# supply.net
KiCad netlist of a schematic drawn in Altium Designer
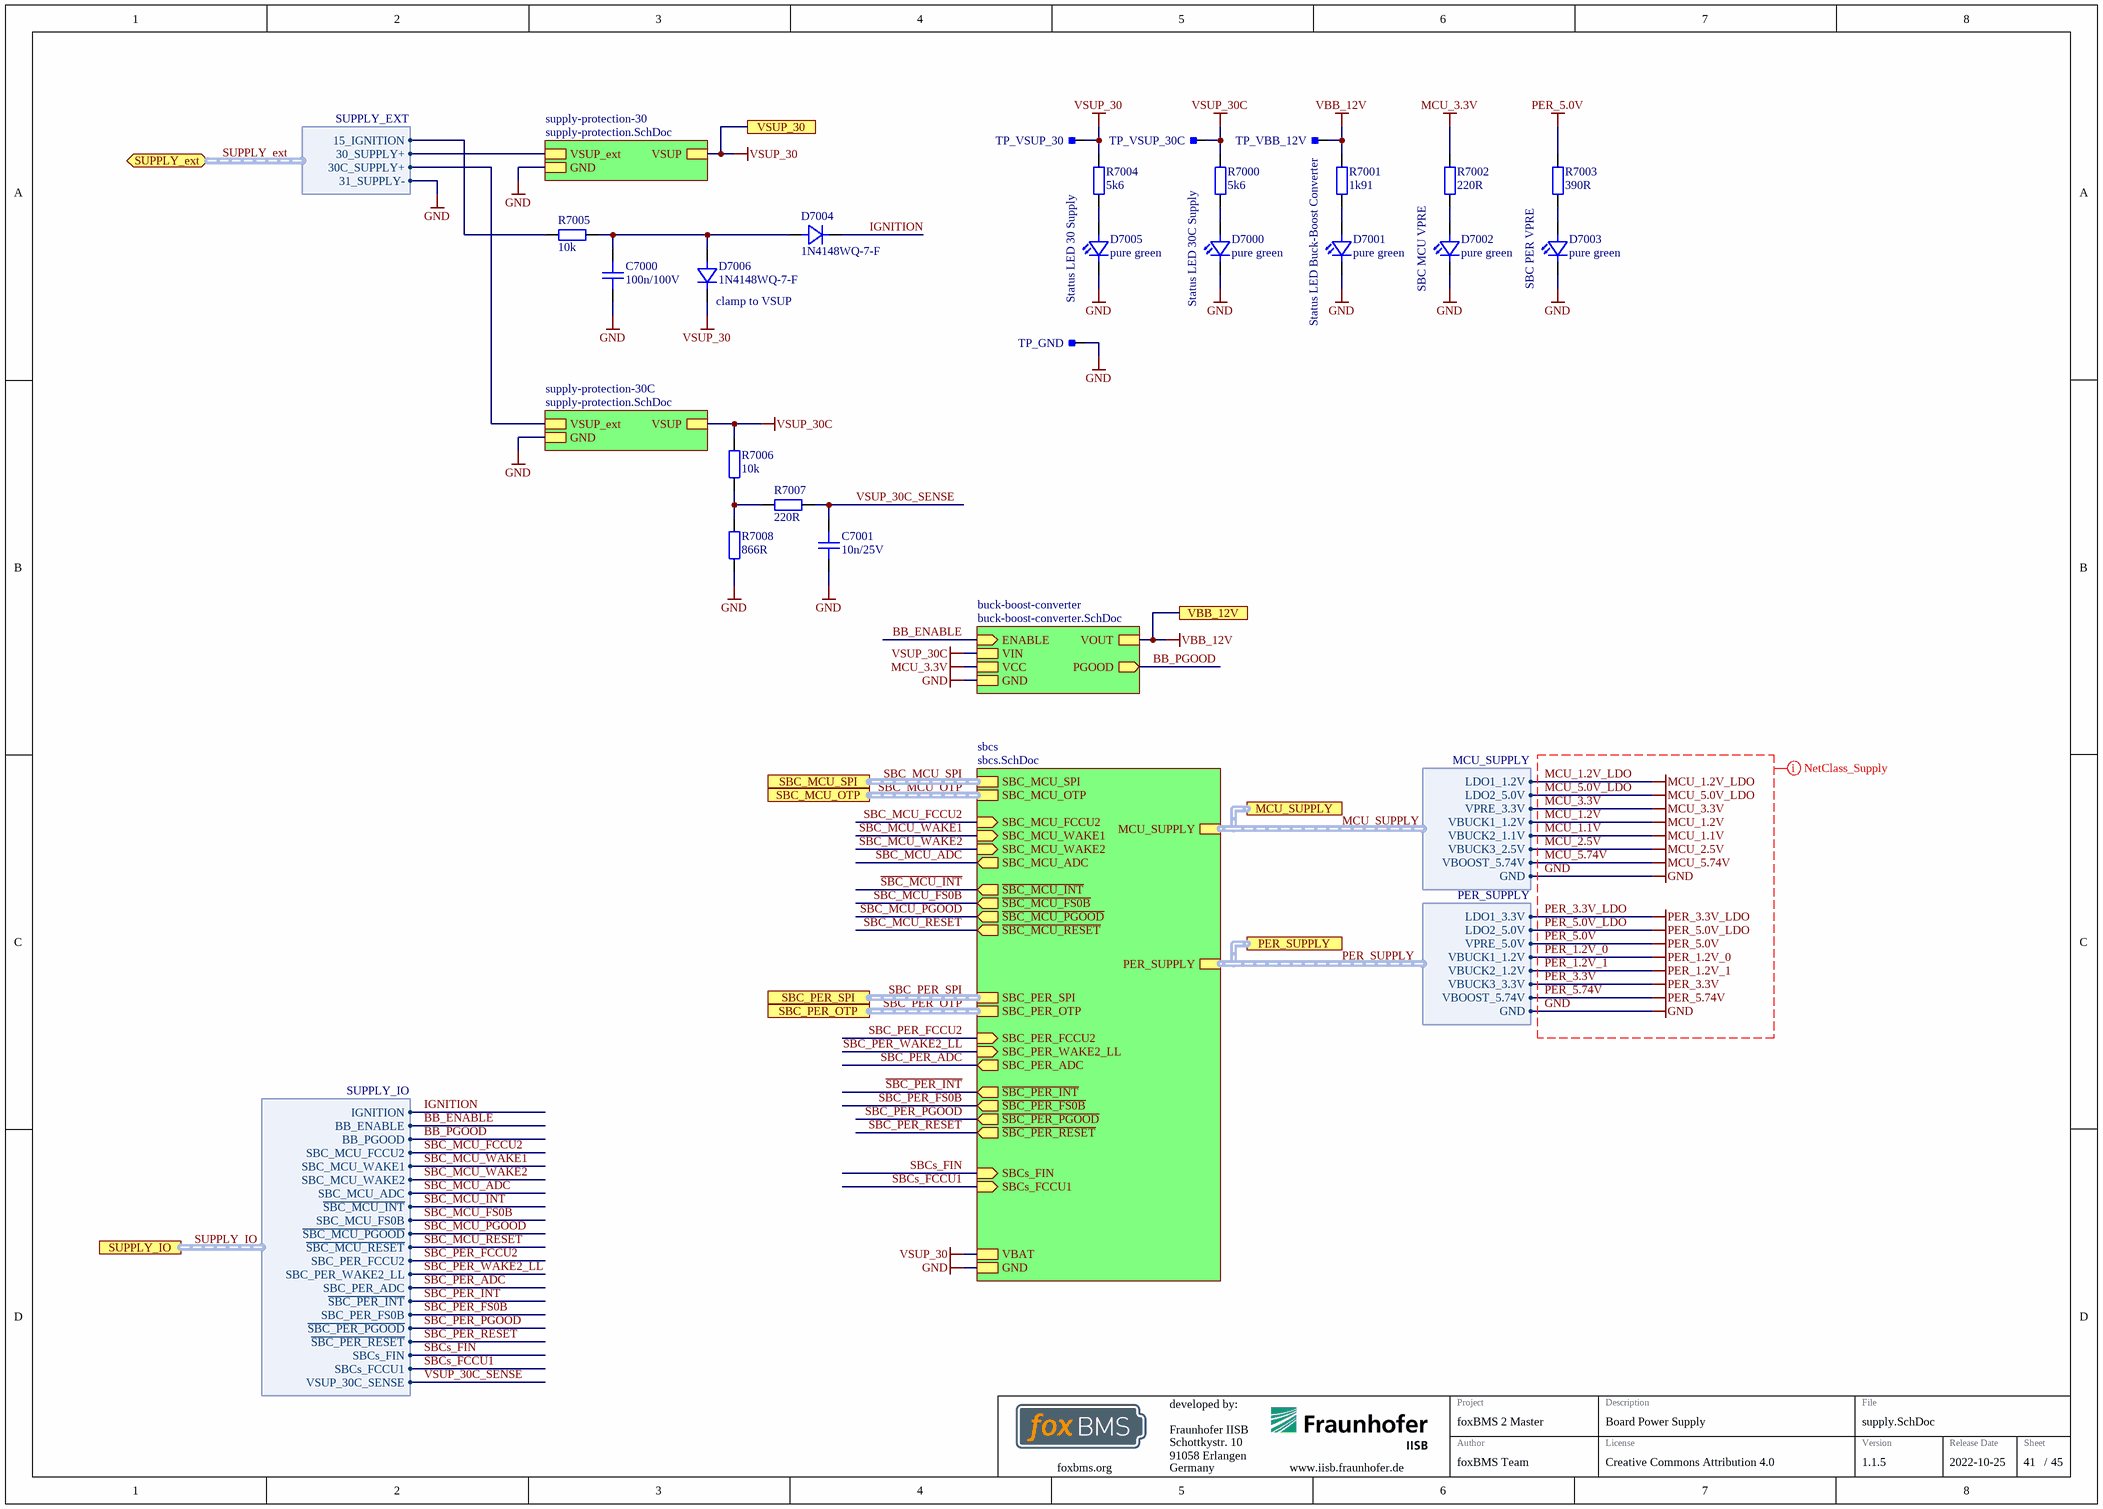
[diagram p0: supply.SchDoc]

(export (version "E")
  (design (tool "Eeschema 10.0.6"))
  (components
    (comp (ref "C7000")
      (value "100n/100V")
      (footprint "CAPC1608X08N")
      (description "MLCC")
      (fields (field (name "PART NUMBER") "gen_C_ceramic_100n_100V_X7R_0603"))
      (libsource (lib "OE750") (part "C"))
    )
    (comp (ref "C7001")
      (value "10n/25V")
      (footprint "CAPC1005X06N")
      (description "MLCC")
      (fields (field (name "PART NUMBER") "gen_C_ceramic_10n_25V_X7R_0402"))
      (libsource (lib "OE750") (part "C"))
    )
    (comp (ref "D7000")
      (value "pure green")
      (footprint "LEDC1608X07N")
      (description "TLMP1100-GS08")
      (fields (field (name "PART NUMBER") "LED_0603_pure_green_AECQ") (field (name "MANUFACTURER") "Vishay"))
      (libsource (lib "OE750") (part "D_LED"))
    )
    (comp (ref "D7001")
      (value "pure green")
      (footprint "LEDC1608X07N")
      (description "TLMP1100-GS08")
      (fields (field (name "PART NUMBER") "LED_0603_pure_green_AECQ") (field (name "MANUFACTURER") "Vishay"))
      (libsource (lib "OE750") (part "D_LED"))
    )
    (comp (ref "D7002")
      (value "pure green")
      (footprint "LEDC1608X07N")
      (description "TLMP1100-GS08")
      (fields (field (name "PART NUMBER") "LED_0603_pure_green_AECQ") (field (name "MANUFACTURER") "Vishay"))
      (libsource (lib "OE750") (part "D_LED"))
    )
    (comp (ref "D7003")
      (value "pure green")
      (footprint "LEDC1608X07N")
      (description "TLMP1100-GS08")
      (fields (field (name "PART NUMBER") "LED_0603_pure_green_AECQ") (field (name "MANUFACTURER") "Vishay"))
      (libsource (lib "OE750") (part "D_LED"))
    )
    (comp (ref "D7004")
      (value "1N4148WQ-7-F")
      (footprint "SOD-123_CASE-425-04-ISSUE-G")
      (description "Diode")
      (fields (field (name "MANUFACTURER") "Diodes Inc."))
      (libsource (lib "OE750") (part "D"))
    )
    (comp (ref "D7005")
      (value "pure green")
      (footprint "LEDC1608X07N")
      (description "TLMP1100-GS08")
      (fields (field (name "PART NUMBER") "LED_0603_pure_green_AECQ") (field (name "MANUFACTURER") "Vishay"))
      (libsource (lib "OE750") (part "D_LED"))
    )
    (comp (ref "D7006")
      (value "1N4148WQ-7-F")
      (footprint "SOD-123_CASE-425-04-ISSUE-G")
      (description "Diode")
      (fields (field (name "MANUFACTURER") "Diodes Inc."))
      (libsource (lib "OE750") (part "D"))
    )
    (comp (ref "R7000")
      (value "5k6")
      (footprint "RESC1005X04N")
      (description "SMD Resistor 5k6 0402")
      (fields (field (name "PART NUMBER") "gen_R_5k6_0402") (field (name "TOLERANCE") "1%"))
      (libsource (lib "OE750") (part "R"))
    )
    (comp (ref "R7001")
      (value "1k91")
      (footprint "RESC1005X04N")
      (description "SMD Resistor 1k91 0402")
      (fields (field (name "PART NUMBER") "gen_R_1k91_0402") (field (name "TOLERANCE") "1%"))
      (libsource (lib "OE750") (part "R"))
    )
    (comp (ref "R7002")
      (value "220R")
      (footprint "RESC1005X04N")
      (description "SMD Resistor 220R 0402")
      (fields (field (name "PART NUMBER") "gen_R_220R_0402") (field (name "TOLERANCE") "1%"))
      (libsource (lib "OE750") (part "R"))
    )
    (comp (ref "R7003")
      (value "390R")
      (footprint "RESC1005X04N")
      (description "SMD Resistor 390R 0402")
      (fields (field (name "PART NUMBER") "gen_R_390R_0402") (field (name "TOLERANCE") "1%"))
      (libsource (lib "OE750") (part "R"))
    )
    (comp (ref "R7004")
      (value "5k6")
      (footprint "RESC1005X04N")
      (description "SMD Resistor 5k6 0402")
      (fields (field (name "PART NUMBER") "gen_R_5k6_0402") (field (name "TOLERANCE") "1%"))
      (libsource (lib "OE750") (part "R"))
    )
    (comp (ref "R7005")
      (value "10k")
      (footprint "RESC1005X04N")
      (description "SMD Resistor 10k 0402")
      (fields (field (name "PART NUMBER") "gen_R_10k_0402") (field (name "TOLERANCE") "1%"))
      (libsource (lib "OE750") (part "R"))
    )
    (comp (ref "R7006")
      (value "10k")
      (footprint "RESC1005X04N")
      (description "SMD Resistor 10k 0402")
      (fields (field (name "PART NUMBER") "gen_R_10k_0402") (field (name "TOLERANCE") "1%"))
      (libsource (lib "OE750") (part "R"))
    )
    (comp (ref "R7007")
      (value "220R")
      (footprint "RESC1005X04N")
      (description "SMD Resistor 220R 0402")
      (fields (field (name "PART NUMBER") "gen_R_220R_0402") (field (name "TOLERANCE") "1%"))
      (libsource (lib "OE750") (part "R"))
    )
    (comp (ref "R7008")
      (value "866R")
      (footprint "RESC1005X04N")
      (description "SMD Resistor 866R 0402")
      (fields (field (name "PART NUMBER") "gen_R_866R_0402") (field (name "TOLERANCE") "1%"))
      (libsource (lib "OE750") (part "R"))
    )
    (comp (ref "TP_GND")
      (value "Testpoint_Square")
      (footprint "Testpoint_S1")
      (description "Testpoint, square")
      (libsource (lib "OE750") (part "Testpoint_Square"))
    )
    (comp (ref "TP_VBB_12V")
      (value "Testpoint_Square")
      (footprint "Testpoint_S1")
      (description "Testpoint, square")
      (libsource (lib "OE750") (part "Testpoint_Square"))
    )
    (comp (ref "TP_VSUP_30")
      (value "Testpoint_Square")
      (footprint "Testpoint_S1")
      (description "Testpoint, square")
      (libsource (lib "OE750") (part "Testpoint_Square"))
    )
    (comp (ref "TP_VSUP_30C")
      (value "Testpoint_Square")
      (footprint "Testpoint_S1")
      (description "Testpoint, square")
      (libsource (lib "OE750") (part "Testpoint_Square"))
    )
  )
  (nets
    (net (code "9") (name "/15_IGNITION") (class "Default")
      (node (ref "R7005") (pin "2") (pinfunction "2_2") (pintype "passive"))
    )
    (net (code "14") (name "/IGNITION") (class "Default")
      (node (ref "D7004") (pin "1") (pinfunction "K_1") (pintype "passive"))
    )
    (net (code "36") (name "/VSUP_30C_SENSE") (class "Default")
      (node (ref "C7001") (pin "2") (pinfunction "2_2") (pintype "passive"))
      (node (ref "R7007") (pin "2") (pinfunction "2_2") (pintype "passive"))
    )
    (net (code "41") (name "GND") (class "Default")
      (node (ref "C7000") (pin "1") (pinfunction "1_1") (pintype "passive"))
      (node (ref "C7001") (pin "1") (pinfunction "1_1") (pintype "passive"))
      (node (ref "D7000") (pin "1") (pinfunction "C_1") (pintype "passive"))
      (node (ref "D7001") (pin "1") (pinfunction "C_1") (pintype "passive"))
      (node (ref "D7002") (pin "1") (pinfunction "C_1") (pintype "passive"))
      (node (ref "D7003") (pin "1") (pinfunction "C_1") (pintype "passive"))
      (node (ref "D7005") (pin "1") (pinfunction "C_1") (pintype "passive"))
      (node (ref "R7008") (pin "1") (pinfunction "1_1") (pintype "passive"))
      (node (ref "TP_GND") (pin "1") (pinfunction "1_1") (pintype "passive"))
    )
    (net (code "46") (name "MCU_3.3V") (class "Default")
      (node (ref "R7002") (pin "2") (pinfunction "2_2") (pintype "passive"))
    )
    (net (code "49") (name "Net-(D7000-A)") (class "Default")
      (node (ref "D7000") (pin "2") (pinfunction "A_2") (pintype "passive"))
      (node (ref "R7000") (pin "1") (pinfunction "1_1") (pintype "passive"))
    )
    (net (code "50") (name "Net-(D7001-A)") (class "Default")
      (node (ref "D7001") (pin "2") (pinfunction "A_2") (pintype "passive"))
      (node (ref "R7001") (pin "1") (pinfunction "1_1") (pintype "passive"))
    )
    (net (code "51") (name "Net-(D7002-A)") (class "Default")
      (node (ref "D7002") (pin "2") (pinfunction "A_2") (pintype "passive"))
      (node (ref "R7002") (pin "1") (pinfunction "1_1") (pintype "passive"))
    )
    (net (code "52") (name "Net-(D7003-A)") (class "Default")
      (node (ref "D7003") (pin "2") (pinfunction "A_2") (pintype "passive"))
      (node (ref "R7003") (pin "1") (pinfunction "1_1") (pintype "passive"))
    )
    (net (code "53") (name "Net-(D7004-A)") (class "Default")
      (node (ref "C7000") (pin "2") (pinfunction "2_2") (pintype "passive"))
      (node (ref "D7004") (pin "2") (pinfunction "A_2") (pintype "passive"))
      (node (ref "D7006") (pin "2") (pinfunction "A_2") (pintype "passive"))
      (node (ref "R7005") (pin "1") (pinfunction "1_1") (pintype "passive"))
    )
    (net (code "54") (name "Net-(D7005-A)") (class "Default")
      (node (ref "D7005") (pin "2") (pinfunction "A_2") (pintype "passive"))
      (node (ref "R7004") (pin "1") (pinfunction "1_1") (pintype "passive"))
    )
    (net (code "55") (name "Net-(R7006-Pad1)") (class "Default")
      (node (ref "R7006") (pin "1") (pinfunction "1_1") (pintype "passive"))
      (node (ref "R7007") (pin "1") (pinfunction "1_1") (pintype "passive"))
      (node (ref "R7008") (pin "2") (pinfunction "2_2") (pintype "passive"))
    )
    (net (code "60") (name "PER_5.0V") (class "Default")
      (node (ref "R7003") (pin "2") (pinfunction "2_2") (pintype "passive"))
    )
    (net (code "63") (name "VBB_12V") (class "Default")
      (node (ref "R7001") (pin "2") (pinfunction "2_2") (pintype "passive"))
      (node (ref "TP_VBB_12V") (pin "1") (pinfunction "1_1") (pintype "passive"))
    )
    (net (code "64") (name "VSUP_30") (class "Default")
      (node (ref "D7006") (pin "1") (pinfunction "K_1") (pintype "passive"))
      (node (ref "R7004") (pin "2") (pinfunction "2_2") (pintype "passive"))
      (node (ref "TP_VSUP_30") (pin "1") (pinfunction "1_1") (pintype "passive"))
    )
    (net (code "65") (name "VSUP_30C") (class "Default")
      (node (ref "R7000") (pin "2") (pinfunction "2_2") (pintype "passive"))
      (node (ref "R7006") (pin "2") (pinfunction "2_2") (pintype "passive"))
      (node (ref "TP_VSUP_30C") (pin "1") (pinfunction "1_1") (pintype "passive"))
    )
  )
)
